# XMOS_TSBOARD_Top.net
KiCad netlist of a schematic drawn in Altium Designer
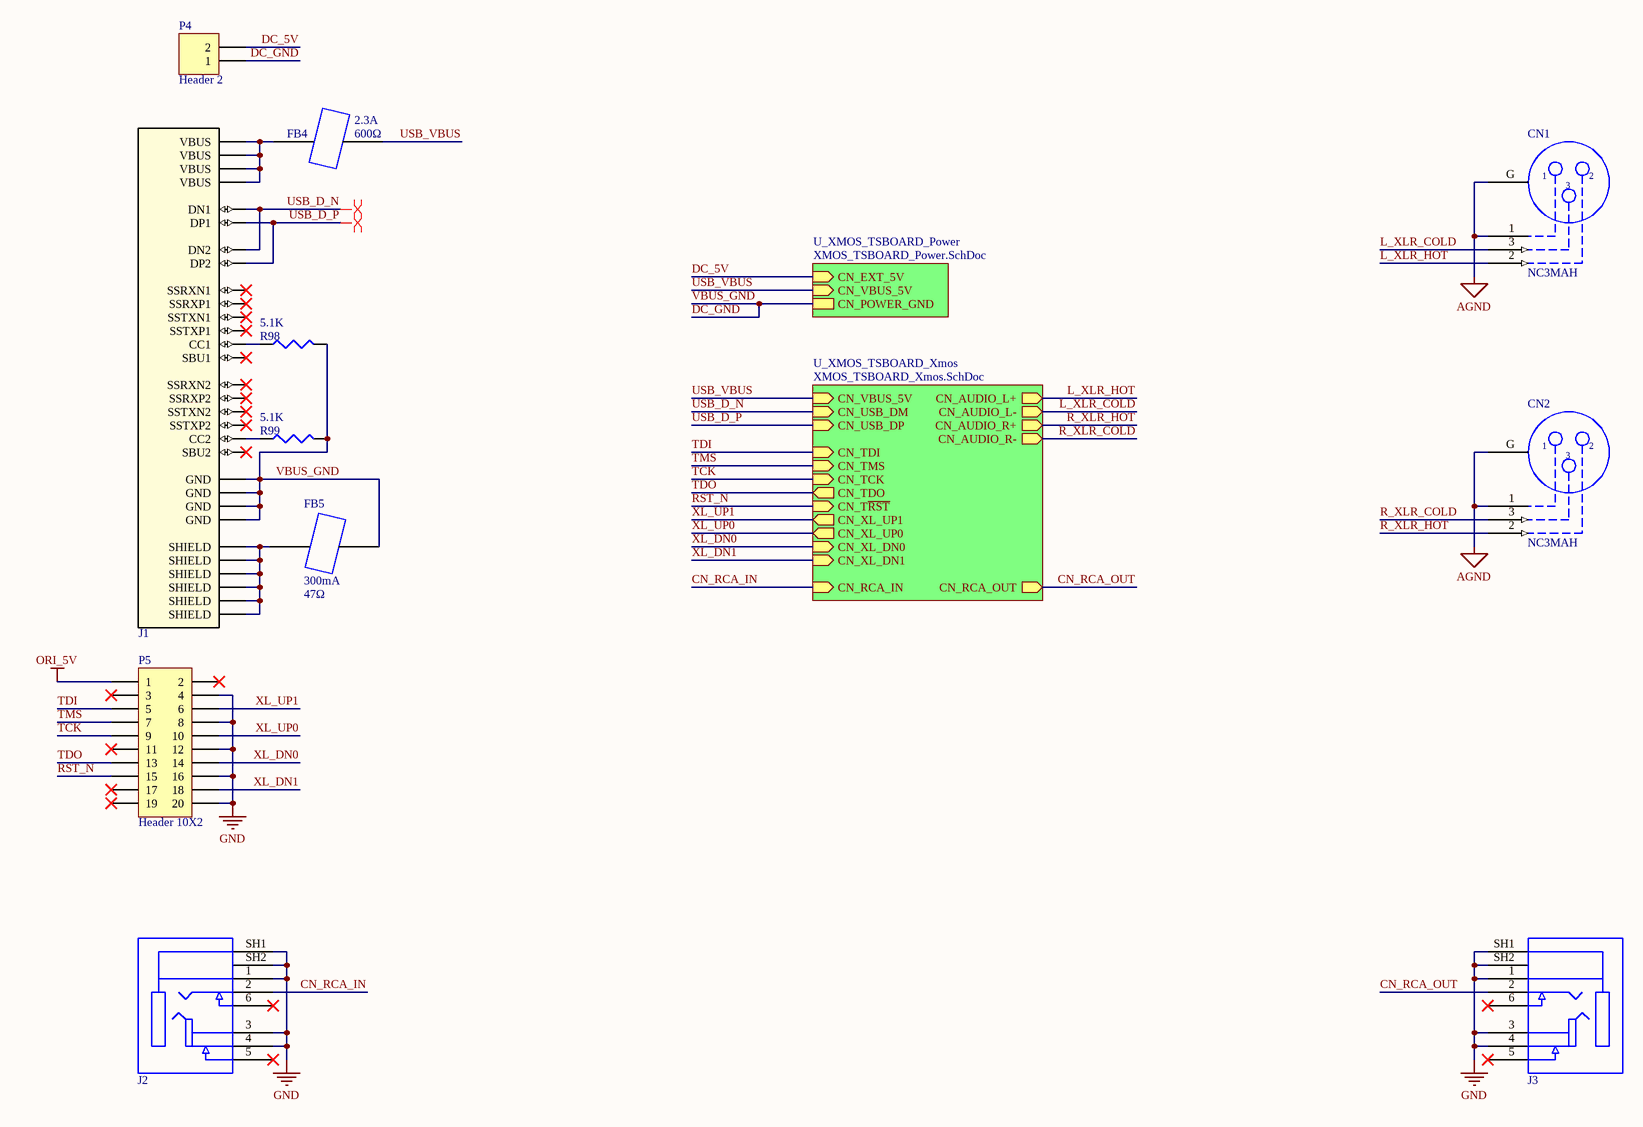
[diagram p0: XMOS_TSBOARD_Top.SchDoc]

(export (version "E")
  (design (tool "Eeschema 10.0.6"))
  (components
    (comp (ref "CN1")
      (value "NC3MAH")
      (footprint "NC3MAH")
      (description "3 pole male XLR receptacle")
      (libsource (lib "Troposphere_lib") (part "NC3MAH"))
    )
    (comp (ref "CN2")
      (value "NC3MAH")
      (footprint "NC3MAH")
      (description "3 pole male XLR receptacle")
      (libsource (lib "Troposphere_lib") (part "NC3MAH"))
    )
    (comp (ref "FB4")
      (value "FerriteBeads")
      (footprint "0805")
      (description "Chip Ferrite Beads")
      (fields (field (name "RATEDCURRENT") "2.3A") (field (name "IMPEDANCE(100MHZ)") "600Ω"))
      (libsource (lib "Troposphere_lib") (part "FerriteBeads"))
    )
    (comp (ref "FB5")
      (value "FerriteBeads")
      (footprint "0603")
      (description "Chip Ferrite Beads")
      (fields (field (name "RATEDCURRENT") "300mA") (field (name "IMPEDANCE(100MHZ)") "47Ω"))
      (libsource (lib "Troposphere_lib") (part "FerriteBeads"))
    )
    (comp (ref "J1")
      (value "UJ31-CH-G1-SMT-TR")
      (footprint "UJ31-CH-G1-SMT-TR")
      (description "USB Type C receptacle")
      (libsource (lib "Troposphere_lib") (part "UJ31-CH-G1-SMT-TR"))
    )
    (comp (ref "J2")
      (value "SJ-3506-SMT-TR")
      (footprint "SJ-3506-SMT-TR")
      (description "Mid Mount Audio Jack")
      (libsource (lib "Troposphere_lib") (part "SJ-3506-SMT-TR"))
    )
    (comp (ref "J3")
      (value "SJ-3506-SMT-TR")
      (footprint "SJ-3506-SMT-TR")
      (description "Mid Mount Audio Jack")
      (libsource (lib "Troposphere_lib") (part "SJ-3506-SMT-TR"))
    )
    (comp (ref "P4")
      (value "Header 2")
      (footprint "HDR1X2")
      (description "Header, 2-Pin")
      (fields (field (name "PUBLISHER") "Altium Limited"))
      (libsource (lib "Miscellaneous Connectors") (part "Header 2"))
    )
    (comp (ref "P5")
      (value "Header 10X2")
      (footprint "HDR2X10")
      (description "Header, 10-Pin, Dual row")
      (fields (field (name "PUBLISHER") "Altium Limited"))
      (libsource (lib "Miscellaneous Connectors") (part "Header 10X2"))
    )
    (comp (ref "R98")
      (value "5.1K")
      (footprint "J1-0603")
      (description "Resistor")
      (fields (field (name "Comment") "Res3") (field (name "PUBLISHER") "Altium Limited"))
      (libsource (lib "Miscellaneous Devices") (part "Res3"))
    )
    (comp (ref "R99")
      (value "5.1K")
      (footprint "J1-0603")
      (description "Resistor")
      (fields (field (name "Comment") "Res3") (field (name "PUBLISHER") "Altium Limited"))
      (libsource (lib "Miscellaneous Devices") (part "Res3"))
    )
  )
  (nets
    (net (code "1") (name "/CN_RCA_IN") (class "Default")
      (node (ref "J2") (pin "2") (pinfunction "TIP_2") (pintype "passive"))
    )
    (net (code "2") (name "/CN_RCA_OUT") (class "Default")
      (node (ref "J3") (pin "2") (pinfunction "TIP_2") (pintype "passive"))
    )
    (net (code "3") (name "/DC_5V") (class "Default")
      (node (ref "P4") (pin "2") (pinfunction "2_2") (pintype "passive"))
    )
    (net (code "4") (name "/DC_GND") (class "Default")
      (node (ref "FB5") (pin "1") (pinfunction "1_1") (pintype "power_in"))
      (node (ref "J1") (pin "A1") (pinfunction "GND_A1") (pintype "power_in"))
      (node (ref "J1") (pin "A12") (pinfunction "GND_A12") (pintype "power_in"))
      (node (ref "J1") (pin "B1") (pinfunction "GND_B1") (pintype "power_in"))
      (node (ref "J1") (pin "B12") (pinfunction "GND_B12") (pintype "power_in"))
      (node (ref "P4") (pin "1") (pinfunction "1_1") (pintype "passive"))
      (node (ref "R98") (pin "2") (pinfunction "2_2") (pintype "passive"))
      (node (ref "R99") (pin "2") (pinfunction "2_2") (pintype "passive"))
    )
    (net (code "5") (name "/L_XLR_COLD") (class "Default")
      (node (ref "CN1") (pin "3") (pinfunction "3_3") (pintype "input"))
    )
    (net (code "6") (name "/L_XLR_HOT") (class "Default")
      (node (ref "CN1") (pin "2") (pinfunction "2_2") (pintype "input"))
    )
    (net (code "7") (name "/RST_N") (class "Default")
      (node (ref "P5") (pin "15") (pinfunction "15_15") (pintype "passive"))
    )
    (net (code "8") (name "/R_XLR_COLD") (class "Default")
      (node (ref "CN2") (pin "3") (pinfunction "3_3") (pintype "input"))
    )
    (net (code "9") (name "/R_XLR_HOT") (class "Default")
      (node (ref "CN2") (pin "2") (pinfunction "2_2") (pintype "input"))
    )
    (net (code "10") (name "/TCK") (class "Default")
      (node (ref "P5") (pin "9") (pinfunction "9_9") (pintype "passive"))
    )
    (net (code "11") (name "/TDI") (class "Default")
      (node (ref "P5") (pin "5") (pinfunction "5_5") (pintype "passive"))
    )
    (net (code "12") (name "/TDO") (class "Default")
      (node (ref "P5") (pin "13") (pinfunction "13_13") (pintype "passive"))
    )
    (net (code "13") (name "/TMS") (class "Default")
      (node (ref "P5") (pin "7") (pinfunction "7_7") (pintype "passive"))
    )
    (net (code "14") (name "/USB_D_N") (class "Default")
      (node (ref "J1") (pin "A7") (pinfunction "DN1_A7") (pintype "bidirectional"))
      (node (ref "J1") (pin "B7") (pinfunction "DN2_B7") (pintype "bidirectional"))
    )
    (net (code "15") (name "/USB_D_P") (class "Default")
      (node (ref "J1") (pin "A6") (pinfunction "DP1_A6") (pintype "bidirectional"))
      (node (ref "J1") (pin "B6") (pinfunction "DP2_B6") (pintype "bidirectional"))
    )
    (net (code "16") (name "/USB_VBUS") (class "Default")
      (node (ref "FB4") (pin "1") (pinfunction "1_1") (pintype "power_in"))
    )
    (net (code "17") (name "/XL_DN0") (class "Default")
      (node (ref "P5") (pin "14") (pinfunction "14_14") (pintype "passive"))
    )
    (net (code "18") (name "/XL_DN1") (class "Default")
      (node (ref "P5") (pin "18") (pinfunction "18_18") (pintype "passive"))
    )
    (net (code "19") (name "/XL_UP0") (class "Default")
      (node (ref "P5") (pin "10") (pinfunction "10_10") (pintype "passive"))
    )
    (net (code "20") (name "/XL_UP1") (class "Default")
      (node (ref "P5") (pin "6") (pinfunction "6_6") (pintype "passive"))
    )
    (net (code "21") (name "AGND") (class "Default")
      (node (ref "CN1") (pin "1") (pinfunction "1_1") (pintype "power_in"))
      (node (ref "CN1") (pin "G") (pinfunction "G_G") (pintype "power_in"))
      (node (ref "CN2") (pin "1") (pinfunction "1_1") (pintype "power_in"))
      (node (ref "CN2") (pin "G") (pinfunction "G_G") (pintype "power_in"))
    )
    (net (code "22") (name "GND") (class "Default")
      (node (ref "J2") (pin "1") (pinfunction "SLEEVE_1") (pintype "passive"))
      (node (ref "J2") (pin "3") (pinfunction "RING_3") (pintype "passive"))
      (node (ref "J2") (pin "4") (pinfunction "ISOLATED_RING_4") (pintype "passive"))
      (node (ref "J2") (pin "SH1") (pinfunction "SHIELDING_SH1") (pintype "passive"))
      (node (ref "J2") (pin "SH2") (pinfunction "SHIELDING_SH2") (pintype "passive"))
      (node (ref "J3") (pin "1") (pinfunction "SLEEVE_1") (pintype "passive"))
      (node (ref "J3") (pin "3") (pinfunction "RING_3") (pintype "passive"))
      (node (ref "J3") (pin "4") (pinfunction "ISOLATED_RING_4") (pintype "passive"))
      (node (ref "J3") (pin "SH1") (pinfunction "SHIELDING_SH1") (pintype "passive"))
      (node (ref "J3") (pin "SH2") (pinfunction "SHIELDING_SH2") (pintype "passive"))
      (node (ref "P5") (pin "12") (pinfunction "12_12") (pintype "passive"))
      (node (ref "P5") (pin "16") (pinfunction "16_16") (pintype "passive"))
      (node (ref "P5") (pin "20") (pinfunction "20_20") (pintype "passive"))
      (node (ref "P5") (pin "4") (pinfunction "4_4") (pintype "passive"))
      (node (ref "P5") (pin "8") (pinfunction "8_8") (pintype "passive"))
    )
    (net (code "23") (name "Net-(FB4-Pad2)") (class "Default")
      (node (ref "FB4") (pin "2") (pinfunction "2_2") (pintype "power_in"))
      (node (ref "J1") (pin "A4") (pinfunction "VBUS_A4") (pintype "power_in"))
      (node (ref "J1") (pin "A9") (pinfunction "VBUS_A9") (pintype "power_in"))
      (node (ref "J1") (pin "B4") (pinfunction "VBUS_B4") (pintype "power_in"))
      (node (ref "J1") (pin "B9") (pinfunction "VBUS_B9") (pintype "power_in"))
    )
    (net (code "24") (name "Net-(FB5-Pad2)") (class "Default")
      (node (ref "FB5") (pin "2") (pinfunction "2_2") (pintype "power_in"))
      (node (ref "J1") (pin "SH1") (pinfunction "SHIELD_SH1") (pintype "power_in"))
      (node (ref "J1") (pin "SH2") (pinfunction "SHIELD_SH2") (pintype "power_in"))
      (node (ref "J1") (pin "SH3") (pinfunction "SHIELD_SH3") (pintype "power_in"))
      (node (ref "J1") (pin "SH4") (pinfunction "SHIELD_SH4") (pintype "power_in"))
      (node (ref "J1") (pin "SH5") (pinfunction "SHIELD_SH5") (pintype "power_in"))
      (node (ref "J1") (pin "SH6") (pinfunction "SHIELD_SH6") (pintype "power_in"))
    )
    (net (code "25") (name "Net-(J1-CC1)") (class "Default")
      (node (ref "J1") (pin "A5") (pinfunction "CC1_A5") (pintype "bidirectional"))
      (node (ref "R98") (pin "1") (pinfunction "1_1") (pintype "passive"))
    )
    (net (code "26") (name "Net-(J1-CC2)") (class "Default")
      (node (ref "J1") (pin "B5") (pinfunction "CC2_B5") (pintype "bidirectional"))
      (node (ref "R99") (pin "1") (pinfunction "1_1") (pintype "passive"))
    )
    (net (code "27") (name "ORI_5V") (class "Default")
      (node (ref "P5") (pin "1") (pinfunction "1_1") (pintype "passive"))
    )
    (net (code "28") (name "unconnected-(J1-SBU1-PadA8)") (class "Default")
      (node (ref "J1") (pin "A8") (pinfunction "SBU1_A8") (pintype "bidirectional+no_connect"))
    )
    (net (code "29") (name "unconnected-(J1-SBU2-PadB8)") (class "Default")
      (node (ref "J1") (pin "B8") (pinfunction "SBU2_B8") (pintype "bidirectional+no_connect"))
    )
    (net (code "30") (name "unconnected-(J1-SSRXN1-PadB10)") (class "Default")
      (node (ref "J1") (pin "B10") (pinfunction "SSRXN1_B10") (pintype "bidirectional+no_connect"))
    )
    (net (code "31") (name "unconnected-(J1-SSRXN2-PadA10)") (class "Default")
      (node (ref "J1") (pin "A10") (pinfunction "SSRXN2_A10") (pintype "bidirectional+no_connect"))
    )
    (net (code "32") (name "unconnected-(J1-SSRXP1-PadB11)") (class "Default")
      (node (ref "J1") (pin "B11") (pinfunction "SSRXP1_B11") (pintype "bidirectional+no_connect"))
    )
    (net (code "33") (name "unconnected-(J1-SSRXP2-PadA11)") (class "Default")
      (node (ref "J1") (pin "A11") (pinfunction "SSRXP2_A11") (pintype "bidirectional+no_connect"))
    )
    (net (code "34") (name "unconnected-(J1-SSTXN1-PadA3)") (class "Default")
      (node (ref "J1") (pin "A3") (pinfunction "SSTXN1_A3") (pintype "bidirectional+no_connect"))
    )
    (net (code "35") (name "unconnected-(J1-SSTXN2-PadB3)") (class "Default")
      (node (ref "J1") (pin "B3") (pinfunction "SSTXN2_B3") (pintype "bidirectional+no_connect"))
    )
    (net (code "36") (name "unconnected-(J1-SSTXP1-PadA2)") (class "Default")
      (node (ref "J1") (pin "A2") (pinfunction "SSTXP1_A2") (pintype "bidirectional+no_connect"))
    )
    (net (code "37") (name "unconnected-(J1-SSTXP2-PadB2)") (class "Default")
      (node (ref "J1") (pin "B2") (pinfunction "SSTXP2_B2") (pintype "bidirectional+no_connect"))
    )
    (net (code "38") (name "unconnected-(J2-ISOLATED_RING_SWITCH(N-O)-Pad5)") (class "Default")
      (node (ref "J2") (pin "5") (pinfunction "ISOLATED_RING_SWITCH(N-O)_5") (pintype "passive+no_connect"))
    )
    (net (code "39") (name "unconnected-(J2-TIP_SWITCH-Pad6)") (class "Default")
      (node (ref "J2") (pin "6") (pinfunction "TIP_SWITCH_6") (pintype "passive+no_connect"))
    )
    (net (code "40") (name "unconnected-(J3-ISOLATED_RING_SWITCH(N-O)-Pad5)") (class "Default")
      (node (ref "J3") (pin "5") (pinfunction "ISOLATED_RING_SWITCH(N-O)_5") (pintype "passive+no_connect"))
    )
    (net (code "41") (name "unconnected-(J3-TIP_SWITCH-Pad6)") (class "Default")
      (node (ref "J3") (pin "6") (pinfunction "TIP_SWITCH_6") (pintype "passive+no_connect"))
    )
    (net (code "42") (name "unconnected-(P5-Pad2)") (class "Default")
      (node (ref "P5") (pin "2") (pinfunction "2_2") (pintype "passive+no_connect"))
    )
    (net (code "43") (name "unconnected-(P5-Pad3)") (class "Default")
      (node (ref "P5") (pin "3") (pinfunction "3_3") (pintype "passive+no_connect"))
    )
    (net (code "44") (name "unconnected-(P5-Pad11)") (class "Default")
      (node (ref "P5") (pin "11") (pinfunction "11_11") (pintype "passive+no_connect"))
    )
    (net (code "45") (name "unconnected-(P5-Pad17)") (class "Default")
      (node (ref "P5") (pin "17") (pinfunction "17_17") (pintype "passive+no_connect"))
    )
    (net (code "46") (name "unconnected-(P5-Pad19)") (class "Default")
      (node (ref "P5") (pin "19") (pinfunction "19_19") (pintype "passive+no_connect"))
    )
  )
)
